# 3g_PCIe_breakout.net
KiCad netlist of a schematic drawn in EAGLE
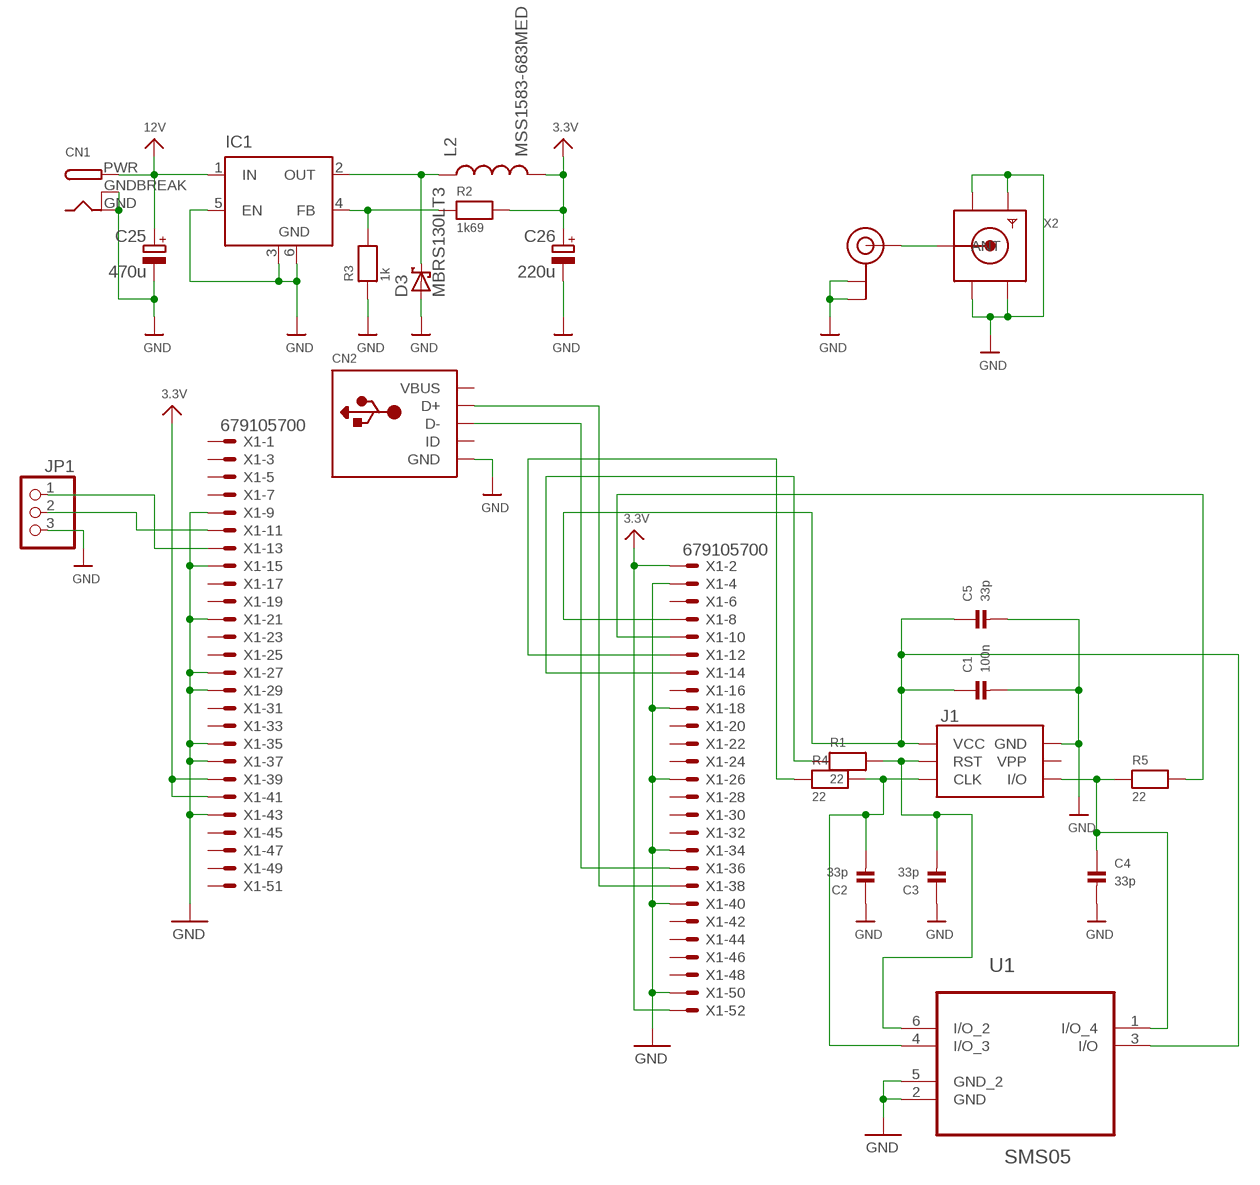
[diagram p0: schematic, sheet 1]

(export (version "E")
  (design (tool "Eeschema 10.0.6"))
  (components
    (comp (ref "C1")
      (value "100n")
      (footprint "eagle-import:_0603")
      (libsource (lib "eagle-import") (part "CAP_CERAMIC_0603"))
    )
    (comp (ref "C2")
      (value "33p")
      (footprint "eagle-import:_0603")
      (libsource (lib "eagle-import") (part "CAP_CERAMIC_0603"))
    )
    (comp (ref "C3")
      (value "33p")
      (footprint "eagle-import:_0603")
      (libsource (lib "eagle-import") (part "CAP_CERAMIC_0603"))
    )
    (comp (ref "C4")
      (value "33p")
      (footprint "eagle-import:_0603")
      (libsource (lib "eagle-import") (part "CAP_CERAMIC_0603"))
    )
    (comp (ref "C5")
      (value "33p")
      (footprint "eagle-import:_0603")
      (libsource (lib "eagle-import") (part "CAP_CERAMIC_0603"))
    )
    (comp (ref "C25")
      (value "470u")
      (footprint "eagle-import:153CLV-1012")
      (libsource (lib "eagle-import") (part "CPOL-EU153CLV-1012"))
    )
    (comp (ref "C26")
      (value "220u")
      (footprint "eagle-import:153CLV-1012")
      (libsource (lib "eagle-import") (part "CPOL-EU153CLV-1012"))
    )
    (comp (ref "CN1")
      (value "DCBARRELPTH")
      (footprint "eagle-import:DCJACK_2MM_PTH")
      (libsource (lib "eagle-import") (part "DCBARRELPTH"))
    )
    (comp (ref "CN2")
      (value "USBMINIB")
      (footprint "eagle-import:USB-MINIB")
      (libsource (lib "eagle-import") (part "USBMINIB"))
    )
    (comp (ref "D3")
      (value "MBRS130LT3")
      (footprint "eagle-import:SMB")
      (libsource (lib "eagle-import") (part "MBRS130LT3"))
    )
    (comp (ref "IC1")
      (value "LM2596S")
      (footprint "eagle-import:TO263-5")
      (libsource (lib "eagle-import") (part "LM2596S"))
    )
    (comp (ref "J1")
      (value "SIMHOLDERSIM")
      (footprint "eagle-import:SIMHOLDER")
      (libsource (lib "eagle-import") (part "SIMHOLDERSIM"))
    )
    (comp (ref "JP1")
      (value "PINHD-1X3")
      (footprint "eagle-import:1X03")
      (libsource (lib "eagle-import") (part "PINHD-1X3"))
    )
    (comp (ref "L2")
      (value "MSS1583-683MED")
      (footprint "eagle-import:CDRH125")
      (libsource (lib "eagle-import") (part "INDUCTORPWR"))
    )
    (comp (ref "R1")
      (value "22")
      (footprint "eagle-import:_0603")
      (libsource (lib "eagle-import") (part "RESISTOR_0603"))
    )
    (comp (ref "R2")
      (value "1k69")
      (footprint "eagle-import:_0603")
      (libsource (lib "eagle-import") (part "RESISTOR_0603"))
    )
    (comp (ref "R3")
      (value "1k")
      (footprint "eagle-import:_0603")
      (libsource (lib "eagle-import") (part "RESISTOR_0603"))
    )
    (comp (ref "R4")
      (value "22")
      (footprint "eagle-import:_0603")
      (libsource (lib "eagle-import") (part "RESISTOR_0603"))
    )
    (comp (ref "R5")
      (value "22")
      (footprint "eagle-import:_0603")
      (libsource (lib "eagle-import") (part "RESISTOR_0603"))
    )
    (comp (ref "U$12")
      (value "U.FL")
      (footprint "eagle-import:U.FL")
      (libsource (lib "eagle-import") (part "U.FL"))
    )
    (comp (ref "U1")
      (value "SMS05")
      (footprint "eagle-import:SOT95P280X145-6N")
      (libsource (lib "eagle-import") (part "SMS05"))
    )
    (comp (ref "X1")
      (value "679105700")
      (footprint "eagle-import:679105700")
      (fields (field (name "MPN") "67910-5700"))
      (libsource (lib "eagle-import") (part "679105700"))
    )
    (comp (ref "X2")
      (value "SMACONNECTOR")
      (footprint "eagle-import:SMA90_DIP")
      (libsource (lib "eagle-import") (part "SMACONNECTOR"))
    )
  )
  (nets
    (net (code "1") (name "/VBUS") (class "Default")
      (node (ref "CN2") (pin "VBUS") (pinfunction "VBUS_VBUS") (pintype "power_in"))
    )
    (net (code "2") (name "3.3V") (class "Default")
      (node (ref "C26") (pin "+") (pinfunction "+_+") (pintype "passive"))
      (node (ref "L2") (pin "2") (pinfunction "2_2") (pintype "passive"))
      (node (ref "R2") (pin "2") (pinfunction "2_2") (pintype "passive"))
      (node (ref "X1") (pin "2") (pinfunction "S_2") (pintype "passive"))
      (node (ref "X1") (pin "39") (pinfunction "S_39") (pintype "passive"))
      (node (ref "X1") (pin "41") (pinfunction "S_41") (pintype "passive"))
      (node (ref "X1") (pin "52") (pinfunction "S_52") (pintype "passive"))
    )
    (net (code "3") (name "12V") (class "Default")
      (node (ref "C25") (pin "+") (pinfunction "+_+") (pintype "passive"))
      (node (ref "CN1") (pin "PWR") (pinfunction "PWR_PWR") (pintype "power_in"))
      (node (ref "IC1") (pin "1") (pinfunction "IN_1") (pintype "input"))
    )
    (net (code "4") (name "GND") (class "Default")
      (node (ref "C1") (pin "2") (pinfunction "P$2_2") (pintype "passive"))
      (node (ref "C2") (pin "1") (pinfunction "P$1_1") (pintype "passive"))
      (node (ref "C25") (pin "-") (pinfunction "-_-") (pintype "passive"))
      (node (ref "C26") (pin "-") (pinfunction "-_-") (pintype "passive"))
      (node (ref "C3") (pin "1") (pinfunction "P$1_1") (pintype "passive"))
      (node (ref "C4") (pin "2") (pinfunction "P$2_2") (pintype "passive"))
      (node (ref "C5") (pin "2") (pinfunction "P$2_2") (pintype "passive"))
      (node (ref "CN1") (pin "GND") (pinfunction "GND_GND") (pintype "power_in"))
      (node (ref "CN1") (pin "GNDBREAK") (pinfunction "GNDBREAK_GNDBREAK") (pintype "power_in"))
      (node (ref "CN2") (pin "GND") (pinfunction "GND_GND") (pintype "power_in"))
      (node (ref "D3") (pin "A") (pinfunction "A_A") (pintype "passive"))
      (node (ref "IC1") (pin "3") (pinfunction "GND_3") (pintype "power_in"))
      (node (ref "IC1") (pin "5") (pinfunction "EN_5") (pintype "input"))
      (node (ref "IC1") (pin "6") (pinfunction "GND_6") (pintype "power_in"))
      (node (ref "J1") (pin "C5") (pinfunction "GND_C5") (pintype "power_in"))
      (node (ref "JP1") (pin "3") (pinfunction "3_3") (pintype "passive"))
      (node (ref "R3") (pin "1") (pinfunction "1_1") (pintype "passive"))
      (node (ref "U$12") (pin "1") (pinfunction "GND_1") (pintype "passive"))
      (node (ref "U$12") (pin "2") (pinfunction "GND_2") (pintype "passive"))
      (node (ref "U1") (pin "2") (pinfunction "GND_2") (pintype "passive"))
      (node (ref "U1") (pin "5") (pinfunction "GND_2_5") (pintype "passive"))
      (node (ref "X1") (pin "15") (pinfunction "S_15") (pintype "passive"))
      (node (ref "X1") (pin "18") (pinfunction "S_18") (pintype "passive"))
      (node (ref "X1") (pin "21") (pinfunction "S_21") (pintype "passive"))
      (node (ref "X1") (pin "26") (pinfunction "S_26") (pintype "passive"))
      (node (ref "X1") (pin "27") (pinfunction "S_27") (pintype "passive"))
      (node (ref "X1") (pin "29") (pinfunction "S_29") (pintype "passive"))
      (node (ref "X1") (pin "34") (pinfunction "S_34") (pintype "passive"))
      (node (ref "X1") (pin "35") (pinfunction "S_35") (pintype "passive"))
      (node (ref "X1") (pin "37") (pinfunction "S_37") (pintype "passive"))
      (node (ref "X1") (pin "4") (pinfunction "S_4") (pintype "passive"))
      (node (ref "X1") (pin "40") (pinfunction "S_40") (pintype "passive"))
      (node (ref "X1") (pin "43") (pinfunction "S_43") (pintype "passive"))
      (node (ref "X1") (pin "50") (pinfunction "S_50") (pintype "passive"))
      (node (ref "X1") (pin "9") (pinfunction "S_9") (pintype "passive"))
      (node (ref "X2") (pin "GND1") (pinfunction "GND1_GND1") (pintype "power_in"))
      (node (ref "X2") (pin "GND2") (pinfunction "GND2_GND2") (pintype "power_in"))
      (node (ref "X2") (pin "GND3") (pinfunction "GND3_GND3") (pintype "power_in"))
      (node (ref "X2") (pin "GND4") (pinfunction "GND4_GND4") (pintype "power_in"))
    )
    (net (code "5") (name "Net-(C1-P$1)") (class "Default")
      (node (ref "C1") (pin "1") (pinfunction "P$1_1") (pintype "passive"))
      (node (ref "C5") (pin "1") (pinfunction "P$1_1") (pintype "passive"))
      (node (ref "J1") (pin "C1") (pinfunction "VCC_C1") (pintype "power_in"))
      (node (ref "U1") (pin "3") (pinfunction "I/O_3") (pintype "bidirectional"))
      (node (ref "X1") (pin "8") (pinfunction "S_8") (pintype "passive"))
    )
    (net (code "6") (name "Net-(C2-P$2)") (class "Default")
      (node (ref "C2") (pin "2") (pinfunction "P$2_2") (pintype "passive"))
      (node (ref "J1") (pin "C3") (pinfunction "CLK_C3") (pintype "input"))
      (node (ref "R4") (pin "2") (pinfunction "2_2") (pintype "passive"))
      (node (ref "U1") (pin "4") (pinfunction "I/O_3_4") (pintype "bidirectional"))
    )
    (net (code "7") (name "Net-(C3-P$2)") (class "Default")
      (node (ref "C3") (pin "2") (pinfunction "P$2_2") (pintype "passive"))
      (node (ref "J1") (pin "C2") (pinfunction "RST_C2") (pintype "input"))
      (node (ref "R1") (pin "2") (pinfunction "2_2") (pintype "passive"))
      (node (ref "U1") (pin "6") (pinfunction "I/O_2_6") (pintype "bidirectional"))
    )
    (net (code "8") (name "Net-(C4-P$1)") (class "Default")
      (node (ref "C4") (pin "1") (pinfunction "P$1_1") (pintype "passive"))
      (node (ref "J1") (pin "C7") (pinfunction "I/O_C7") (pintype "bidirectional"))
      (node (ref "R5") (pin "1") (pinfunction "1_1") (pintype "passive"))
      (node (ref "U1") (pin "1") (pinfunction "I/O_4_1") (pintype "bidirectional"))
    )
    (net (code "9") (name "Net-(IC1-FB)") (class "Default")
      (node (ref "IC1") (pin "4") (pinfunction "FB_4") (pintype "input"))
      (node (ref "R2") (pin "1") (pinfunction "1_1") (pintype "passive"))
      (node (ref "R3") (pin "2") (pinfunction "2_2") (pintype "passive"))
    )
    (net (code "10") (name "Net-(IC1-OUT)") (class "Default")
      (node (ref "D3") (pin "C") (pinfunction "C_C") (pintype "passive"))
      (node (ref "IC1") (pin "2") (pinfunction "OUT_2") (pintype "output"))
      (node (ref "L2") (pin "1") (pinfunction "1_1") (pintype "passive"))
    )
    (net (code "11") (name "Net-(U$12-SIGNAL)") (class "Default")
      (node (ref "U$12") (pin "3") (pinfunction "SIGNAL_3") (pintype "passive"))
      (node (ref "X2") (pin "ANTENNA") (pinfunction "ANT_ANTENNA") (pintype "bidirectional"))
    )
    (net (code "12") (name "Net-(X1AD-S)") (class "Default")
      (node (ref "CN2") (pin "D-") (pinfunction "D-_D-") (pintype "bidirectional"))
      (node (ref "X1") (pin "36") (pinfunction "S_36") (pintype "passive"))
    )
    (net (code "13") (name "Net-(X1AF-S)") (class "Default")
      (node (ref "CN2") (pin "D+") (pinfunction "D+_D+") (pintype "bidirectional"))
      (node (ref "X1") (pin "38") (pinfunction "S_38") (pintype "passive"))
    )
    (net (code "14") (name "Net-(X1B-S)") (class "Default")
      (node (ref "R5") (pin "2") (pinfunction "2_2") (pintype "passive"))
      (node (ref "X1") (pin "10") (pinfunction "S_10") (pintype "passive"))
    )
    (net (code "15") (name "Net-(X1C-S)") (class "Default")
      (node (ref "JP1") (pin "2") (pinfunction "2_2") (pintype "passive"))
      (node (ref "X1") (pin "11") (pinfunction "S_11") (pintype "passive"))
    )
    (net (code "16") (name "Net-(X1D-S)") (class "Default")
      (node (ref "R4") (pin "1") (pinfunction "1_1") (pintype "passive"))
      (node (ref "X1") (pin "12") (pinfunction "S_12") (pintype "passive"))
    )
    (net (code "17") (name "Net-(X1E-S)") (class "Default")
      (node (ref "JP1") (pin "1") (pinfunction "1_1") (pintype "passive"))
      (node (ref "X1") (pin "13") (pinfunction "S_13") (pintype "passive"))
    )
    (net (code "18") (name "Net-(X1F-S)") (class "Default")
      (node (ref "R1") (pin "1") (pinfunction "1_1") (pintype "passive"))
      (node (ref "X1") (pin "14") (pinfunction "S_14") (pintype "passive"))
    )
    (net (code "19") (name "unconnected-(CN2-PadID)") (class "Default")
      (node (ref "CN2") (pin "ID") (pinfunction "ID_ID") (pintype "bidirectional"))
    )
    (net (code "20") (name "unconnected-(J1-VPP-PadC6)") (class "Default")
      (node (ref "J1") (pin "C6") (pinfunction "VPP_C6") (pintype "input"))
    )
    (net (code "21") (name "unconnected-(X1A-S-Pad1)") (class "Default")
      (node (ref "X1") (pin "1") (pinfunction "S_1") (pintype "passive"))
    )
    (net (code "22") (name "unconnected-(X1AA-S-Pad33)") (class "Default")
      (node (ref "X1") (pin "33") (pinfunction "S_33") (pintype "passive"))
    )
    (net (code "23") (name "unconnected-(X1AK-S-Pad42)") (class "Default")
      (node (ref "X1") (pin "42") (pinfunction "S_42") (pintype "passive"))
    )
    (net (code "24") (name "unconnected-(X1AM-S-Pad44)") (class "Default")
      (node (ref "X1") (pin "44") (pinfunction "S_44") (pintype "passive"))
    )
    (net (code "25") (name "unconnected-(X1AN-S-Pad45)") (class "Default")
      (node (ref "X1") (pin "45") (pinfunction "S_45") (pintype "passive"))
    )
    (net (code "26") (name "unconnected-(X1AO-S-Pad46)") (class "Default")
      (node (ref "X1") (pin "46") (pinfunction "S_46") (pintype "passive"))
    )
    (net (code "27") (name "unconnected-(X1AP-S-Pad47)") (class "Default")
      (node (ref "X1") (pin "47") (pinfunction "S_47") (pintype "passive"))
    )
    (net (code "28") (name "unconnected-(X1AQ-S-Pad48)") (class "Default")
      (node (ref "X1") (pin "48") (pinfunction "S_48") (pintype "passive"))
    )
    (net (code "29") (name "unconnected-(X1AR-S-Pad49)") (class "Default")
      (node (ref "X1") (pin "49") (pinfunction "S_49") (pintype "passive"))
    )
    (net (code "30") (name "unconnected-(X1AS-S-Pad5)") (class "Default")
      (node (ref "X1") (pin "5") (pinfunction "S_5") (pintype "passive"))
    )
    (net (code "31") (name "unconnected-(X1AU-S-Pad51)") (class "Default")
      (node (ref "X1") (pin "51") (pinfunction "S_51") (pintype "passive"))
    )
    (net (code "32") (name "unconnected-(X1AW-S-Pad6)") (class "Default")
      (node (ref "X1") (pin "6") (pinfunction "S_6") (pintype "passive"))
    )
    (net (code "33") (name "unconnected-(X1AX-S-Pad7)") (class "Default")
      (node (ref "X1") (pin "7") (pinfunction "S_7") (pintype "passive"))
    )
    (net (code "34") (name "unconnected-(X1H-S-Pad16)") (class "Default")
      (node (ref "X1") (pin "16") (pinfunction "S_16") (pintype "passive"))
    )
    (net (code "35") (name "unconnected-(X1I-S-Pad17)") (class "Default")
      (node (ref "X1") (pin "17") (pinfunction "S_17") (pintype "passive"))
    )
    (net (code "36") (name "unconnected-(X1K-S-Pad19)") (class "Default")
      (node (ref "X1") (pin "19") (pinfunction "S_19") (pintype "passive"))
    )
    (net (code "37") (name "unconnected-(X1M-S-Pad20)") (class "Default")
      (node (ref "X1") (pin "20") (pinfunction "S_20") (pintype "passive"))
    )
    (net (code "38") (name "unconnected-(X1O-S-Pad22)") (class "Default")
      (node (ref "X1") (pin "22") (pinfunction "S_22") (pintype "passive"))
    )
    (net (code "39") (name "unconnected-(X1P-S-Pad23)") (class "Default")
      (node (ref "X1") (pin "23") (pinfunction "S_23") (pintype "passive"))
    )
    (net (code "40") (name "unconnected-(X1Q-S-Pad24)") (class "Default")
      (node (ref "X1") (pin "24") (pinfunction "S_24") (pintype "passive"))
    )
    (net (code "41") (name "unconnected-(X1R-S-Pad25)") (class "Default")
      (node (ref "X1") (pin "25") (pinfunction "S_25") (pintype "passive"))
    )
    (net (code "42") (name "unconnected-(X1U-S-Pad28)") (class "Default")
      (node (ref "X1") (pin "28") (pinfunction "S_28") (pintype "passive"))
    )
    (net (code "43") (name "unconnected-(X1W-S-Pad3)") (class "Default")
      (node (ref "X1") (pin "3") (pinfunction "S_3") (pintype "passive"))
    )
    (net (code "44") (name "unconnected-(X1X-S-Pad30)") (class "Default")
      (node (ref "X1") (pin "30") (pinfunction "S_30") (pintype "passive"))
    )
    (net (code "45") (name "unconnected-(X1Y-S-Pad31)") (class "Default")
      (node (ref "X1") (pin "31") (pinfunction "S_31") (pintype "passive"))
    )
    (net (code "46") (name "unconnected-(X1Z-S-Pad32)") (class "Default")
      (node (ref "X1") (pin "32") (pinfunction "S_32") (pintype "passive"))
    )
  )
)
